# iv12-driver-board-v1.net
KiCad netlist of a schematic drawn in EAGLE
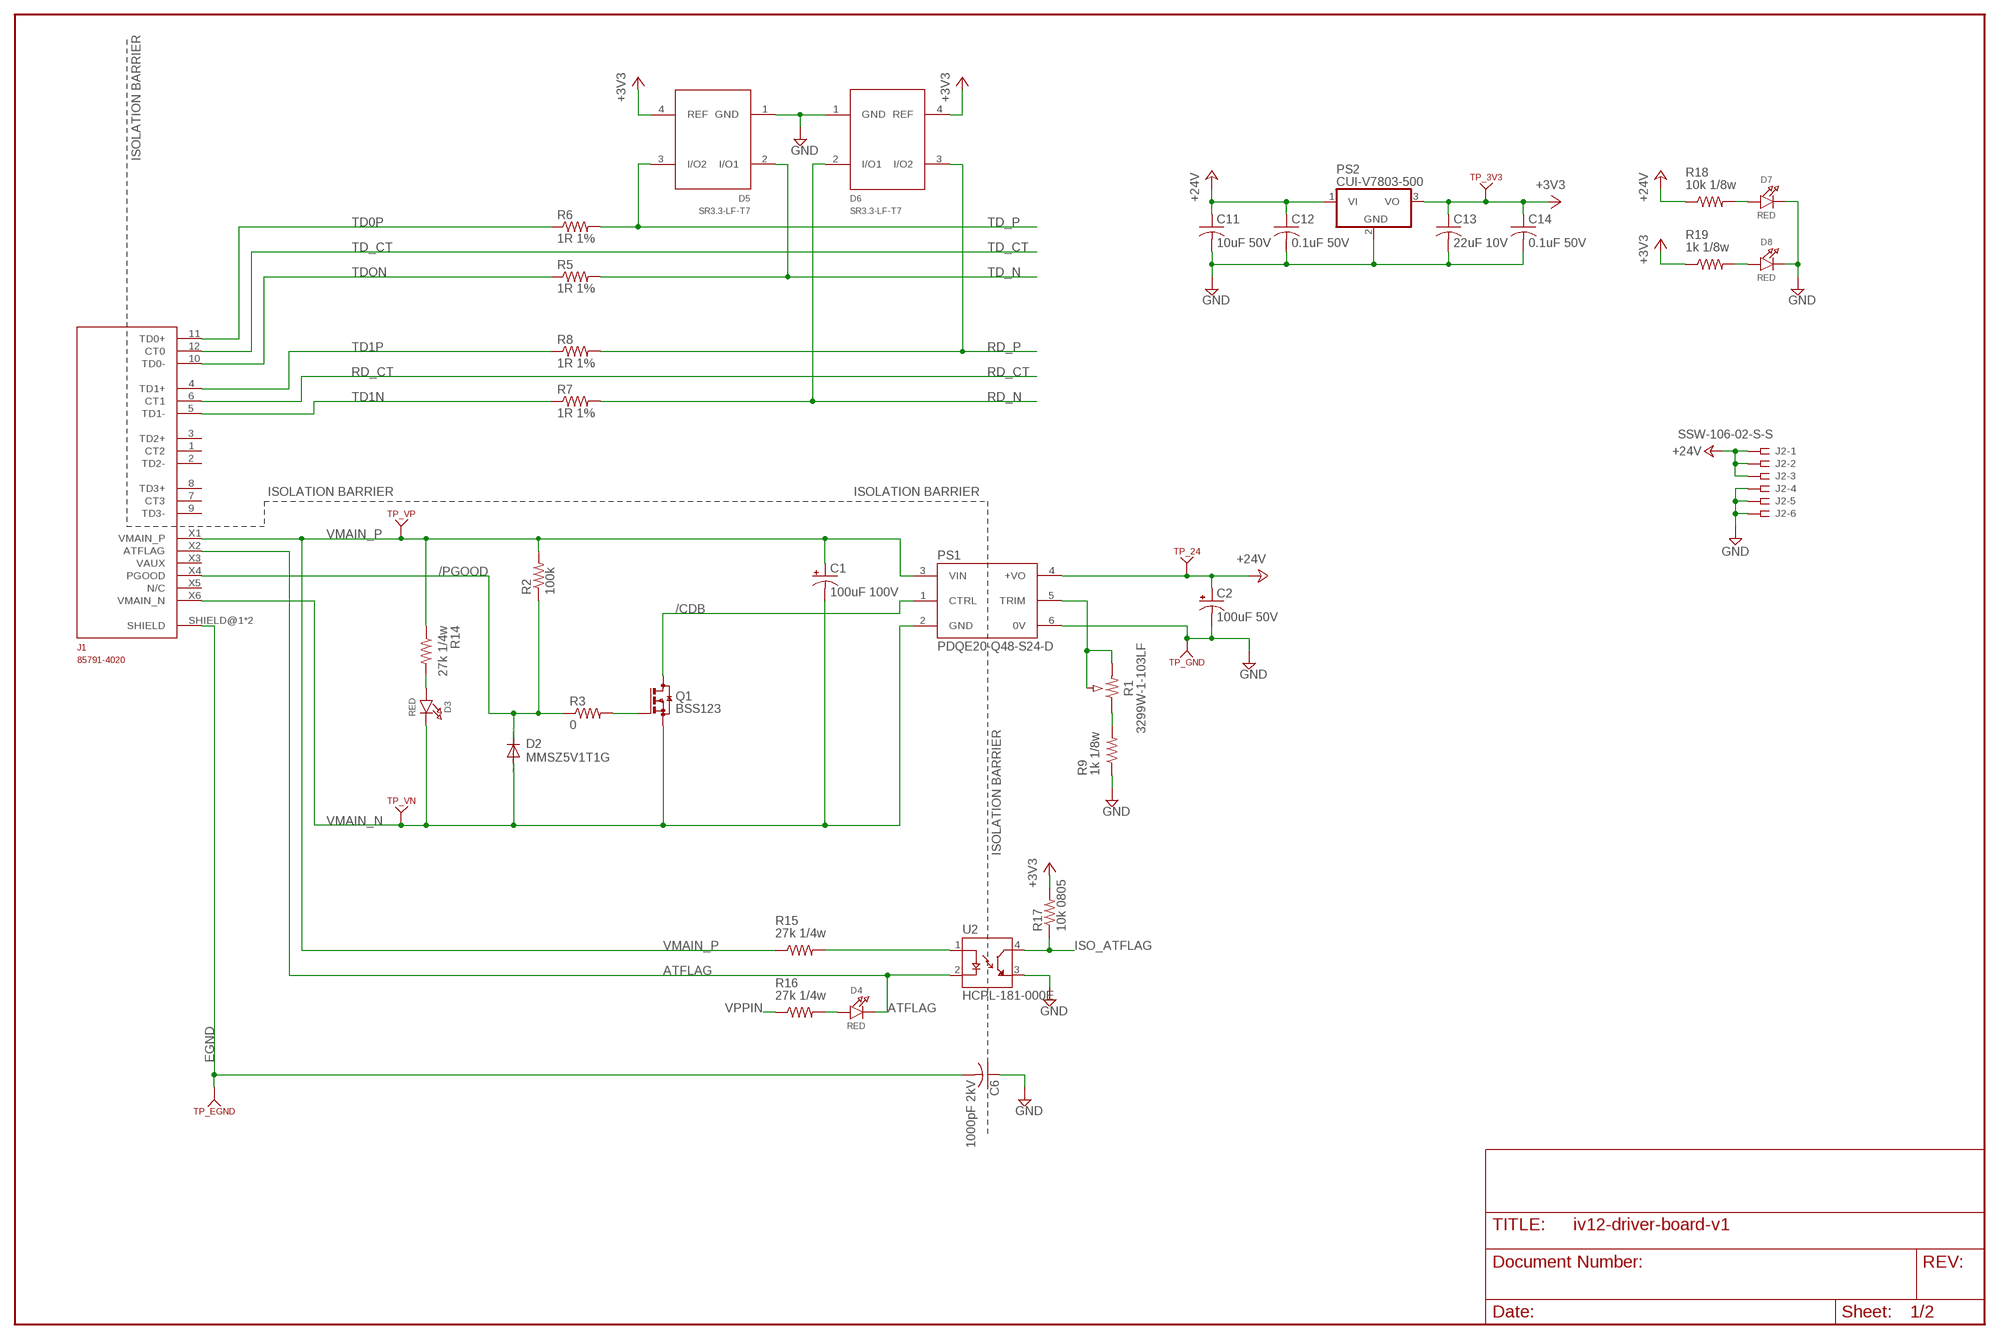
[diagram p0: schematic, sheet 1]
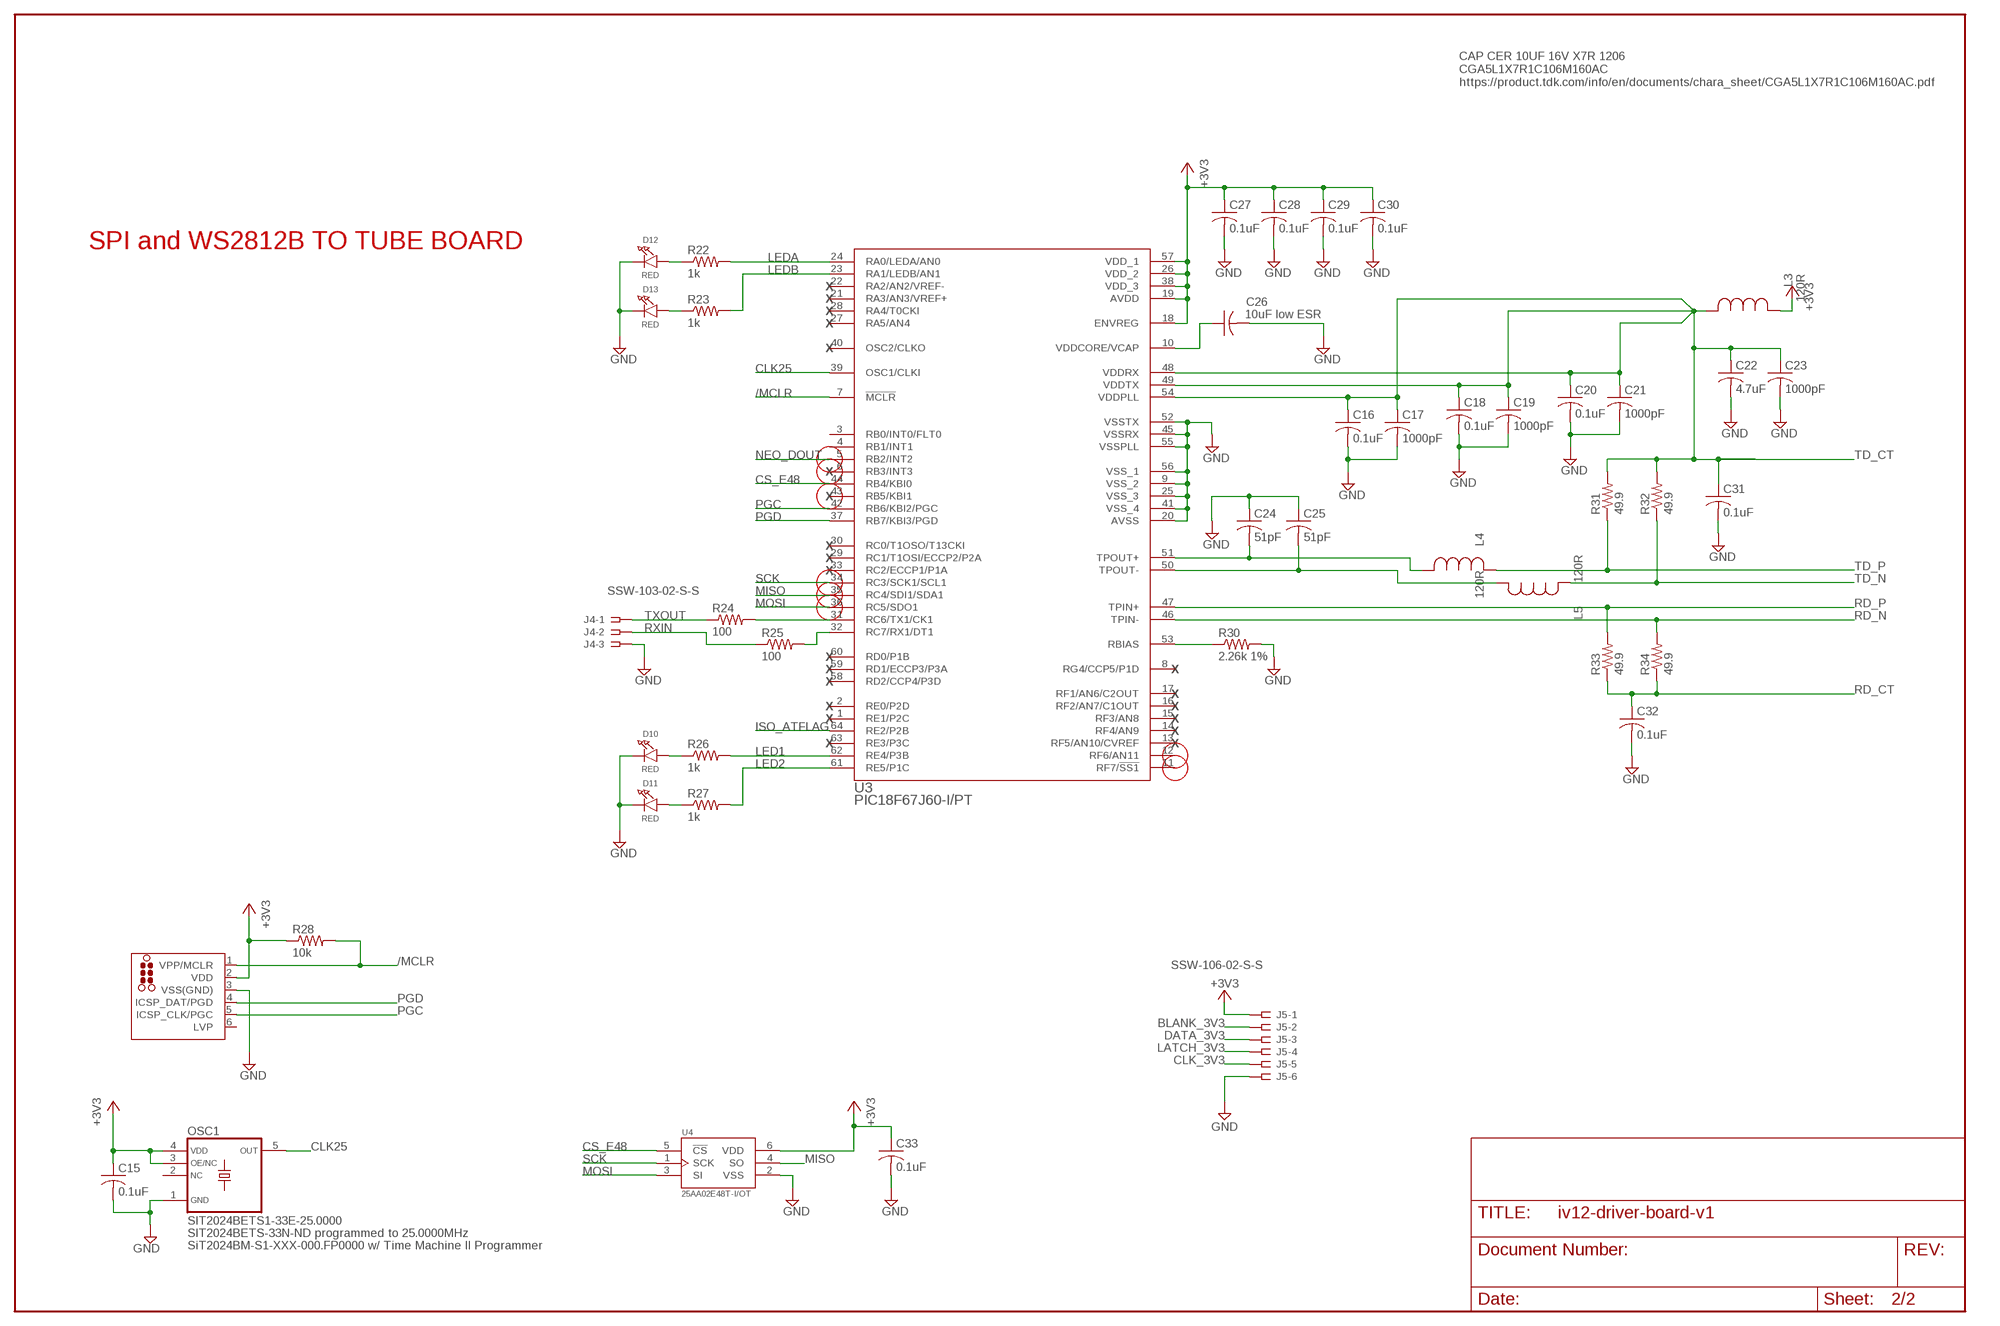
[diagram p1: schematic, sheet 2]

(export (version "E")
  (design (tool "Eeschema 10.0.6"))
  (components
    (comp (ref "C15")
      (value "0.1uF")
      (footprint "eagle-import:C0603")
      (libsource (lib "eagle-import") (part "C-USC0603"))
    )
    (comp (ref "C16")
      (value "0.1uF")
      (footprint "eagle-import:C0805")
      (libsource (lib "eagle-import") (part "C-USC0805"))
    )
    (comp (ref "C17")
      (value "1000pF")
      (footprint "eagle-import:C0805")
      (libsource (lib "eagle-import") (part "C-USC0805"))
    )
    (comp (ref "C18")
      (value "0.1uF")
      (footprint "eagle-import:C0805")
      (libsource (lib "eagle-import") (part "C-USC0805"))
    )
    (comp (ref "C19")
      (value "1000pF")
      (footprint "eagle-import:C0805")
      (libsource (lib "eagle-import") (part "C-USC0805"))
    )
    (comp (ref "C20")
      (value "0.1uF")
      (footprint "eagle-import:C0805")
      (libsource (lib "eagle-import") (part "C-USC0805"))
    )
    (comp (ref "C21")
      (value "1000pF")
      (footprint "eagle-import:C0805")
      (libsource (lib "eagle-import") (part "C-USC0805"))
    )
    (comp (ref "C22")
      (value "4.7uF")
      (footprint "eagle-import:C0805")
      (libsource (lib "eagle-import") (part "C-USC0805"))
    )
    (comp (ref "C23")
      (value "1000pF")
      (footprint "eagle-import:C0805")
      (libsource (lib "eagle-import") (part "C-USC0805"))
    )
    (comp (ref "C24")
      (value "51pF")
      (footprint "eagle-import:C0805")
      (libsource (lib "eagle-import") (part "C-USC0805"))
    )
    (comp (ref "C25")
      (value "51pF")
      (footprint "eagle-import:C0805")
      (libsource (lib "eagle-import") (part "C-USC0805"))
    )
    (comp (ref "C26")
      (value "10uF low ESR")
      (footprint "eagle-import:C1206")
      (libsource (lib "eagle-import") (part "resistor_C-USC1206"))
    )
    (comp (ref "C27")
      (value "0.1uF")
      (footprint "eagle-import:C0603")
      (libsource (lib "eagle-import") (part "C-USC0603"))
    )
    (comp (ref "C28")
      (value "0.1uF")
      (footprint "eagle-import:C0603")
      (libsource (lib "eagle-import") (part "C-USC0603"))
    )
    (comp (ref "C29")
      (value "0.1uF")
      (footprint "eagle-import:C0603")
      (libsource (lib "eagle-import") (part "C-USC0603"))
    )
    (comp (ref "C30")
      (value "0.1uF")
      (footprint "eagle-import:C0603")
      (libsource (lib "eagle-import") (part "C-USC0603"))
    )
    (comp (ref "C31")
      (value "0.1uF")
      (footprint "eagle-import:C0805")
      (libsource (lib "eagle-import") (part "C-USC0805"))
    )
    (comp (ref "C32")
      (value "0.1uF")
      (footprint "eagle-import:C0805")
      (libsource (lib "eagle-import") (part "C-USC0805"))
    )
    (comp (ref "C33")
      (value "0.1uF")
      (footprint "eagle-import:C0603")
      (libsource (lib "eagle-import") (part "C-USC0603"))
    )
    (comp (ref "D10")
      (value "RED")
      (footprint "eagle-import:CHIPLED_0805_NOOUTLINE")
      (libsource (lib "eagle-import") (part "LED0805_NOOUTLINE"))
    )
    (comp (ref "D11")
      (value "RED")
      (footprint "eagle-import:CHIPLED_0805_NOOUTLINE")
      (libsource (lib "eagle-import") (part "LED0805_NOOUTLINE"))
    )
    (comp (ref "D12")
      (value "RED")
      (footprint "eagle-import:CHIPLED_0805_NOOUTLINE")
      (libsource (lib "eagle-import") (part "LED0805_NOOUTLINE"))
    )
    (comp (ref "D13")
      (value "RED")
      (footprint "eagle-import:CHIPLED_0805_NOOUTLINE")
      (libsource (lib "eagle-import") (part "LED0805_NOOUTLINE"))
    )
    (comp (ref "J3")
      (value "TC2030-MCP-NL")
      (footprint "eagle-import:TC2030-MCP-NL")
      (libsource (lib "eagle-import") (part "TC2030-MCP-NL"))
    )
    (comp (ref "J4")
      (value "SSW-103-02-S-S")
      (footprint "eagle-import:SSW-103-02-S-S")
      (libsource (lib "eagle-import") (part "SSW-103-02-S-S"))
    )
    (comp (ref "J5")
      (value "SSW-106-02-S-S")
      (footprint "eagle-import:SSW-106-02-S-S")
      (libsource (lib "eagle-import") (part "SSW-106-02-S-S"))
    )
    (comp (ref "L3")
      (value "120R")
      (footprint "eagle-import:IND_1608-M")
      (fields (field (name "MANUFACTURER_PART_NUMBER") "MMZ1608B121CTAH0"))
      (libsource (lib "eagle-import") (part "MMZ1608B121CTAH0IND_1608-M"))
    )
    (comp (ref "L4")
      (value "120R")
      (footprint "eagle-import:IND_1608-M")
      (fields (field (name "MANUFACTURER_PART_NUMBER") "MMZ1608B121CTAH0"))
      (libsource (lib "eagle-import") (part "MMZ1608B121CTAH0IND_1608-M"))
    )
    (comp (ref "L5")
      (value "120R")
      (footprint "eagle-import:IND_1608-M")
      (fields (field (name "MANUFACTURER_PART_NUMBER") "MMZ1608B121CTAH0"))
      (libsource (lib "eagle-import") (part "MMZ1608B121CTAH0IND_1608-M"))
    )
    (comp (ref "OSC1")
      (value "SIT2024BETS1-33E-25.0000")
      (footprint "eagle-import:SOT23-5")
      (libsource (lib "eagle-import") (part "SIT2024BETS1-33E-10.0000"))
    )
    (comp (ref "R22")
      (value "1k")
      (footprint "eagle-import:R0805")
      (libsource (lib "eagle-import") (part "R-US_R0805"))
    )
    (comp (ref "R23")
      (value "1k")
      (footprint "eagle-import:R0805")
      (libsource (lib "eagle-import") (part "R-US_R0805"))
    )
    (comp (ref "R24")
      (value "100")
      (footprint "eagle-import:R0805")
      (libsource (lib "eagle-import") (part "R-US_R0805"))
    )
    (comp (ref "R25")
      (value "100")
      (footprint "eagle-import:R0805")
      (libsource (lib "eagle-import") (part "R-US_R0805"))
    )
    (comp (ref "R26")
      (value "1k")
      (footprint "eagle-import:R0805")
      (libsource (lib "eagle-import") (part "R-US_R0805"))
    )
    (comp (ref "R27")
      (value "1k")
      (footprint "eagle-import:R0805")
      (libsource (lib "eagle-import") (part "R-US_R0805"))
    )
    (comp (ref "R28")
      (value "10k")
      (footprint "eagle-import:R0805")
      (libsource (lib "eagle-import") (part "R-US_R0805"))
    )
    (comp (ref "R30")
      (value "2.26k 1%")
      (footprint "eagle-import:R0805")
      (libsource (lib "eagle-import") (part "R-US_R0805"))
    )
    (comp (ref "R31")
      (value "49.9")
      (footprint "eagle-import:R0805")
      (libsource (lib "eagle-import") (part "R-US_R0805"))
    )
    (comp (ref "R32")
      (value "49.9")
      (footprint "eagle-import:R0805")
      (libsource (lib "eagle-import") (part "R-US_R0805"))
    )
    (comp (ref "R33")
      (value "49.9")
      (footprint "eagle-import:R0805")
      (libsource (lib "eagle-import") (part "R-US_R0805"))
    )
    (comp (ref "R34")
      (value "49.9")
      (footprint "eagle-import:R0805")
      (libsource (lib "eagle-import") (part "R-US_R0805"))
    )
    (comp (ref "U3")
      (value "PIC18F67J60-I/PT")
      (footprint "eagle-import:TQFP64_10X10MC")
      (fields (field (name "MANUFACTURER_PART_NUMBER") "PIC18F67J60IPT"))
      (libsource (lib "eagle-import") (part "PIC18F67J60-I/PT"))
    )
    (comp (ref "U4")
      (value "25AA02E48T-I/OT")
      (footprint "eagle-import:SOT95P270X145-6N")
      (fields (field (name "DIGI-KEY_PART_NUMBER") "25AA02E48T-I/OTCT-ND") (field (name "MF") "Microchip"))
      (libsource (lib "eagle-import") (part "25AA02E48T-I/OT"))
    )
    (comp (ref "C1")
      (value "100uF 100V")
      (footprint "eagle-import:E5-13")
      (libsource (lib "eagle-import") (part "CPOL-USE5-13"))
    )
    (comp (ref "C2")
      (value "100uF 50V")
      (footprint "eagle-import:E5-10,5")
      (libsource (lib "eagle-import") (part "CPOL-USE5-10.5"))
    )
    (comp (ref "C6")
      (value "1000pF 2kV")
      (footprint "eagle-import:C1206K")
      (libsource (lib "eagle-import") (part "C-USC1206K"))
    )
    (comp (ref "C11")
      (value "10uF 50V")
      (footprint "eagle-import:C1210K")
      (fields (field (name "MFR") "KEMET") (field (name "MFR_PART_NO") "C1210C106K5RACTU"))
      (libsource (lib "eagle-import") (part "C-USC1210K"))
    )
    (comp (ref "C12")
      (value "0.1uF 50V")
      (footprint "eagle-import:C0805")
      (fields (field (name "MFR") "KEMET") (field (name "MFR_PART_NO") "C1206S104M5RACTU"))
      (libsource (lib "eagle-import") (part "C-USC0805"))
    )
    (comp (ref "C13")
      (value "22uF 10V")
      (footprint "eagle-import:C1206K")
      (fields (field (name "MFR") "KEMET") (field (name "MFR_PART_NO") "C1206C226K8RAC7800"))
      (libsource (lib "eagle-import") (part "C-USC1206K"))
    )
    (comp (ref "C14")
      (value "0.1uF 50V")
      (footprint "eagle-import:C0805")
      (fields (field (name "MFR") "KEMET") (field (name "MFR_PART_NO") "C1206S104M5RACTU"))
      (libsource (lib "eagle-import") (part "C-USC0805"))
    )
    (comp (ref "D2")
      (value "MMSZ5V1T1G")
      (footprint "eagle-import:SOD123")
      (libsource (lib "eagle-import") (part "DIODE-SOD123"))
    )
    (comp (ref "D3")
      (value "RED")
      (footprint "eagle-import:CHIPLED_0805_NOOUTLINE")
      (libsource (lib "eagle-import") (part "LED0805_NOOUTLINE"))
    )
    (comp (ref "D4")
      (value "RED")
      (footprint "eagle-import:CHIPLED_0805_NOOUTLINE")
      (libsource (lib "eagle-import") (part "LED0805_NOOUTLINE"))
    )
    (comp (ref "D5")
      (value "SR3.3-LF-T7")
      (footprint "eagle-import:SOT143B")
      (libsource (lib "eagle-import") (part "SR3.3-LF-T7"))
    )
    (comp (ref "D6")
      (value "SR3.3-LF-T7")
      (footprint "eagle-import:SOT143B")
      (libsource (lib "eagle-import") (part "SR3.3-LF-T7"))
    )
    (comp (ref "D7")
      (value "RED")
      (footprint "eagle-import:CHIPLED_0805_NOOUTLINE")
      (libsource (lib "eagle-import") (part "LED0805_NOOUTLINE"))
    )
    (comp (ref "D8")
      (value "RED")
      (footprint "eagle-import:CHIPLED_0805_NOOUTLINE")
      (libsource (lib "eagle-import") (part "LED0805_NOOUTLINE"))
    )
    (comp (ref "J1")
      (value "85791-4020")
      (footprint "eagle-import:85791-X020")
      (libsource (lib "eagle-import") (part "85791-4020"))
    )
    (comp (ref "J2")
      (value "SSW-106-02-S-S")
      (footprint "eagle-import:SSW-106-02-S-S")
      (libsource (lib "eagle-import") (part "SSW-106-02-S-S"))
    )
    (comp (ref "PS1")
      (value "PDQE20-Q48-S24-D")
      (footprint "eagle-import:CONV_PDQE20-Q48-S5-D")
      (fields
        (field (name "DIGI-KEY_PART_NUMBER") "102-6272-ND")
        (field (name "MF") "CUI Inc.")
        (field (name "MP") "PDQE20-Q48-S5-D")
      )
      (libsource (lib "eagle-import") (part "PDQE20-Q48-S5-D"))
    )
    (comp (ref "PS2")
      (value "CUI-V7803-500")
      (footprint "eagle-import:CUI-78XX-500")
      (libsource (lib "eagle-import") (part "CUI-V7803-500"))
    )
    (comp (ref "Q1")
      (value "BSS123")
      (footprint "eagle-import:SOT23")
      (libsource (lib "eagle-import") (part "BSS123"))
    )
    (comp (ref "R1")
      (value "3299W-1-103LF")
      (footprint "eagle-import:POT_3299W")
      (libsource (lib "eagle-import") (part "3299W-1-103LF"))
    )
    (comp (ref "R2")
      (value "100k")
      (footprint "eagle-import:R0805")
      (libsource (lib "eagle-import") (part "resistor_R-US_R0805"))
    )
    (comp (ref "R3")
      (value "0")
      (footprint "eagle-import:R0805")
      (libsource (lib "eagle-import") (part "resistor_R-US_R0805"))
    )
    (comp (ref "R5")
      (value "1R 1%")
      (footprint "eagle-import:R0805")
      (libsource (lib "eagle-import") (part "R-US_R0805"))
    )
    (comp (ref "R6")
      (value "1R 1%")
      (footprint "eagle-import:R0805")
      (libsource (lib "eagle-import") (part "R-US_R0805"))
    )
    (comp (ref "R7")
      (value "1R 1%")
      (footprint "eagle-import:R0805")
      (libsource (lib "eagle-import") (part "R-US_R0805"))
    )
    (comp (ref "R8")
      (value "1R 1%")
      (footprint "eagle-import:R0805")
      (libsource (lib "eagle-import") (part "R-US_R0805"))
    )
    (comp (ref "R9")
      (value "1k 1/8w")
      (footprint "eagle-import:R0805")
      (libsource (lib "eagle-import") (part "R-US_R0805"))
    )
    (comp (ref "R14")
      (value "27k 1/4w")
      (footprint "eagle-import:R1206")
      (libsource (lib "eagle-import") (part "R-US_R1206"))
    )
    (comp (ref "R15")
      (value "27k 1/4w")
      (footprint "eagle-import:R1206")
      (libsource (lib "eagle-import") (part "R-US_R1206"))
    )
    (comp (ref "R16")
      (value "27k 1/4w")
      (footprint "eagle-import:R1206")
      (libsource (lib "eagle-import") (part "R-US_R1206"))
    )
    (comp (ref "R17")
      (value "10k 0805")
      (footprint "eagle-import:R0805")
      (libsource (lib "eagle-import") (part "resistor_R-US_R0805"))
    )
    (comp (ref "R18")
      (value "10k 1/8w")
      (footprint "eagle-import:R0805")
      (libsource (lib "eagle-import") (part "R-US_R0805"))
    )
    (comp (ref "R19")
      (value "1k 1/8w")
      (footprint "eagle-import:R0805")
      (libsource (lib "eagle-import") (part "R-US_R0805"))
    )
    (comp (ref "TP_3V3")
      (value "KEYSTONE_500X")
      (footprint "eagle-import:KEYSTONE_TP500X")
      (libsource (lib "eagle-import") (part "KEYSTONE_500X"))
    )
    (comp (ref "TP_24")
      (value "KEYSTONE_500X")
      (footprint "eagle-import:KEYSTONE_TP500X")
      (libsource (lib "eagle-import") (part "KEYSTONE_500X"))
    )
    (comp (ref "TP_EGND")
      (value "KEYSTONE_500X")
      (footprint "eagle-import:KEYSTONE_TP500X")
      (libsource (lib "eagle-import") (part "KEYSTONE_500X"))
    )
    (comp (ref "TP_GND")
      (value "KEYSTONE_500X")
      (footprint "eagle-import:KEYSTONE_TP500X")
      (libsource (lib "eagle-import") (part "KEYSTONE_500X"))
    )
    (comp (ref "TP_VN")
      (value "KEYSTONE_500X")
      (footprint "eagle-import:KEYSTONE_TP500X")
      (libsource (lib "eagle-import") (part "KEYSTONE_500X"))
    )
    (comp (ref "TP_VP")
      (value "KEYSTONE_500X")
      (footprint "eagle-import:KEYSTONE_TP500X")
      (libsource (lib "eagle-import") (part "KEYSTONE_500X"))
    )
    (comp (ref "U2")
      (value "HCPL-181-000E")
      (footprint "eagle-import:SOIC254P675X240-4N")
      (fields (field (name "DIGI-KEY_PART_NUMBER") "516-1646-1-ND") (field (name "MF") "Broadcom Limited"))
      (libsource (lib "eagle-import") (part "HCPL-181-000E"))
    )
  )
  (nets
    (net (code "1") (name "+3V3") (class "Default")
      (node (ref "C13") (pin "1") (pinfunction "1_1") (pintype "passive"))
      (node (ref "C14") (pin "1") (pinfunction "1_1") (pintype "passive"))
      (node (ref "C15") (pin "1") (pinfunction "1_1") (pintype "passive"))
      (node (ref "C27") (pin "1") (pinfunction "1_1") (pintype "passive"))
      (node (ref "C28") (pin "1") (pinfunction "1_1") (pintype "passive"))
      (node (ref "C29") (pin "1") (pinfunction "1_1") (pintype "passive"))
      (node (ref "C30") (pin "1") (pinfunction "1_1") (pintype "passive"))
      (node (ref "C33") (pin "1") (pinfunction "1_1") (pintype "passive"))
      (node (ref "D5") (pin "4") (pinfunction "REF_4") (pintype "bidirectional"))
      (node (ref "D6") (pin "4") (pinfunction "REF_4") (pintype "bidirectional"))
      (node (ref "J3") (pin "2") (pinfunction "VDD_2") (pintype "power_in"))
      (node (ref "J5") (pin "1") (pinfunction "1_1") (pintype "passive"))
      (node (ref "L3") (pin "2") (pinfunction "2_2") (pintype "passive"))
      (node (ref "OSC1") (pin "3") (pinfunction "OE/NC_3") (pintype "bidirectional"))
      (node (ref "OSC1") (pin "4") (pinfunction "VDD_4") (pintype "bidirectional"))
      (node (ref "PS2") (pin "3") (pinfunction "VO_3") (pintype "passive"))
      (node (ref "R17") (pin "2") (pinfunction "2_2") (pintype "passive"))
      (node (ref "R19") (pin "1") (pinfunction "1_1") (pintype "passive"))
      (node (ref "R28") (pin "1") (pinfunction "1_1") (pintype "passive"))
      (node (ref "TP_3V3") (pin "1") (pinfunction "P$1_1") (pintype "bidirectional"))
      (node (ref "U3") (pin "18") (pinfunction "ENVREG_18") (pintype "passive"))
      (node (ref "U3") (pin "19") (pinfunction "AVDD_19") (pintype "passive"))
      (node (ref "U3") (pin "26") (pinfunction "VDD_2_26") (pintype "passive"))
      (node (ref "U3") (pin "38") (pinfunction "VDD_3_38") (pintype "passive"))
      (node (ref "U3") (pin "57") (pinfunction "VDD_1_57") (pintype "passive"))
      (node (ref "U4") (pin "6") (pinfunction "VDD_6") (pintype "power_in"))
    )
    (net (code "2") (name "+24V") (class "Default")
      (node (ref "C11") (pin "1") (pinfunction "1_1") (pintype "passive"))
      (node (ref "C12") (pin "1") (pinfunction "1_1") (pintype "passive"))
      (node (ref "C2") (pin "+") (pinfunction "+_+") (pintype "passive"))
      (node (ref "J2") (pin "1") (pinfunction "1_1") (pintype "passive"))
      (node (ref "J2") (pin "2") (pinfunction "1_2") (pintype "passive"))
      (node (ref "J2") (pin "3") (pinfunction "1_3") (pintype "passive"))
      (node (ref "PS1") (pin "4") (pinfunction "+VO_4") (pintype "output"))
      (node (ref "PS2") (pin "1") (pinfunction "VI_1") (pintype "input"))
      (node (ref "R18") (pin "1") (pinfunction "1_1") (pintype "passive"))
      (node (ref "TP_24") (pin "1") (pinfunction "P$1_1") (pintype "bidirectional"))
    )
    (net (code "3") (name "ATFLAG") (class "Default")
      (node (ref "D4") (pin "C") (pinfunction "C_C") (pintype "passive"))
      (node (ref "J1") (pin "X2") (pinfunction "ATFLAG_X2") (pintype "bidirectional"))
      (node (ref "U2") (pin "2") (pinfunction "CATHODE_2") (pintype "passive"))
    )
    (net (code "4") (name "BLANK_3V3") (class "Default")
      (node (ref "J5") (pin "2") (pinfunction "1_2") (pintype "passive"))
    )
    (net (code "5") (name "CLK25") (class "Default")
      (node (ref "OSC1") (pin "5") (pinfunction "OUT_5") (pintype "bidirectional"))
      (node (ref "U3") (pin "39") (pinfunction "OSC1/CLKI_39") (pintype "passive"))
    )
    (net (code "6") (name "CLK_3V3") (class "Default")
      (node (ref "J5") (pin "5") (pinfunction "1_5") (pintype "passive"))
    )
    (net (code "7") (name "CS_E48") (class "Default")
      (node (ref "U3") (pin "44") (pinfunction "RB4/KBI0_44") (pintype "passive"))
      (node (ref "U4") (pin "5") (pinfunction "~{CS}_5") (pintype "input"))
    )
    (net (code "8") (name "DATA_3V3") (class "Default")
      (node (ref "J5") (pin "3") (pinfunction "1_3") (pintype "passive"))
    )
    (net (code "9") (name "EGND") (class "Default")
      (node (ref "C6") (pin "2") (pinfunction "2_2") (pintype "passive"))
      (node (ref "J1") (pin "SHIELD@1") (pinfunction "SHIELD_SHIELD@1") (pintype "bidirectional"))
      (node (ref "J1") (pin "SHIELD@2") (pinfunction "SHIELD_SHIELD@2") (pintype "bidirectional"))
      (node (ref "TP_EGND") (pin "1") (pinfunction "P$1_1") (pintype "bidirectional"))
    )
    (net (code "10") (name "GND") (class "Default")
      (node (ref "C11") (pin "2") (pinfunction "2_2") (pintype "passive"))
      (node (ref "C12") (pin "2") (pinfunction "2_2") (pintype "passive"))
      (node (ref "C13") (pin "2") (pinfunction "2_2") (pintype "passive"))
      (node (ref "C14") (pin "2") (pinfunction "2_2") (pintype "passive"))
      (node (ref "C15") (pin "2") (pinfunction "2_2") (pintype "passive"))
      (node (ref "C16") (pin "2") (pinfunction "2_2") (pintype "passive"))
      (node (ref "C17") (pin "2") (pinfunction "2_2") (pintype "passive"))
      (node (ref "C18") (pin "2") (pinfunction "2_2") (pintype "passive"))
      (node (ref "C19") (pin "2") (pinfunction "2_2") (pintype "passive"))
      (node (ref "C2") (pin "-") (pinfunction "-_-") (pintype "passive"))
      (node (ref "C20") (pin "2") (pinfunction "2_2") (pintype "passive"))
      (node (ref "C21") (pin "2") (pinfunction "2_2") (pintype "passive"))
      (node (ref "C22") (pin "2") (pinfunction "2_2") (pintype "passive"))
      (node (ref "C23") (pin "2") (pinfunction "2_2") (pintype "passive"))
      (node (ref "C24") (pin "1") (pinfunction "1_1") (pintype "passive"))
      (node (ref "C25") (pin "1") (pinfunction "1_1") (pintype "passive"))
      (node (ref "C26") (pin "2") (pinfunction "2_2") (pintype "passive"))
      (node (ref "C27") (pin "2") (pinfunction "2_2") (pintype "passive"))
      (node (ref "C28") (pin "2") (pinfunction "2_2") (pintype "passive"))
      (node (ref "C29") (pin "2") (pinfunction "2_2") (pintype "passive"))
      (node (ref "C30") (pin "2") (pinfunction "2_2") (pintype "passive"))
      (node (ref "C31") (pin "2") (pinfunction "2_2") (pintype "passive"))
      (node (ref "C32") (pin "2") (pinfunction "2_2") (pintype "passive"))
      (node (ref "C33") (pin "2") (pinfunction "2_2") (pintype "passive"))
      (node (ref "C6") (pin "1") (pinfunction "1_1") (pintype "passive"))
      (node (ref "D10") (pin "C") (pinfunction "C_C") (pintype "passive"))
      (node (ref "D11") (pin "C") (pinfunction "C_C") (pintype "passive"))
      (node (ref "D12") (pin "C") (pinfunction "C_C") (pintype "passive"))
      (node (ref "D13") (pin "C") (pinfunction "C_C") (pintype "passive"))
      (node (ref "D5") (pin "1") (pinfunction "GND_1") (pintype "bidirectional"))
      (node (ref "D6") (pin "1") (pinfunction "GND_1") (pintype "bidirectional"))
      (node (ref "D7") (pin "C") (pinfunction "C_C") (pintype "passive"))
      (node (ref "D8") (pin "C") (pinfunction "C_C") (pintype "passive"))
      (node (ref "J2") (pin "4") (pinfunction "1_4") (pintype "passive"))
      (node (ref "J2") (pin "5") (pinfunction "1_5") (pintype "passive"))
      (node (ref "J2") (pin "6") (pinfunction "1_6") (pintype "passive"))
      (node (ref "J3") (pin "3") (pinfunction "VSS(GND)_3") (pintype "power_in"))
      (node (ref "J4") (pin "3") (pinfunction "1_3") (pintype "passive"))
      (node (ref "J5") (pin "6") (pinfunction "1_6") (pintype "passive"))
      (node (ref "OSC1") (pin "1") (pinfunction "GND_1") (pintype "bidirectional"))
      (node (ref "PS1") (pin "6") (pinfunction "0V_6") (pintype "output"))
      (node (ref "PS2") (pin "2") (pinfunction "GND_2") (pintype "passive"))
      (node (ref "R30") (pin "2") (pinfunction "2_2") (pintype "passive"))
      (node (ref "R9") (pin "1") (pinfunction "1_1") (pintype "passive"))
      (node (ref "TP_GND") (pin "1") (pinfunction "P$1_1") (pintype "bidirectional"))
      (node (ref "U2") (pin "3") (pinfunction "EMITTER_3") (pintype "passive"))
      (node (ref "U3") (pin "20") (pinfunction "AVSS_20") (pintype "passive"))
      (node (ref "U3") (pin "25") (pinfunction "VSS_3_25") (pintype "passive"))
      (node (ref "U3") (pin "41") (pinfunction "VSS_4_41") (pintype "passive"))
      (node (ref "U3") (pin "45") (pinfunction "VSSRX_45") (pintype "passive"))
      (node (ref "U3") (pin "52") (pinfunction "VSSTX_52") (pintype "passive"))
      (node (ref "U3") (pin "55") (pinfunction "VSSPLL_55") (pintype "passive"))
      (node (ref "U3") (pin "56") (pinfunction "VSS_1_56") (pintype "passive"))
      (node (ref "U3") (pin "9") (pinfunction "VSS_2_9") (pintype "passive"))
      (node (ref "U4") (pin "2") (pinfunction "VSS_2") (pintype "power_in"))
    )
    (net (code "11") (name "ISO_ATFLAG") (class "Default")
      (node (ref "R17") (pin "1") (pinfunction "1_1") (pintype "passive"))
      (node (ref "U2") (pin "4") (pinfunction "COLLECTOR_4") (pintype "passive"))
      (node (ref "U3") (pin "64") (pinfunction "RE2/P2B_64") (pintype "passive"))
    )
    (net (code "12") (name "LATCH_3V3") (class "Default")
      (node (ref "J5") (pin "4") (pinfunction "1_4") (pintype "passive"))
    )
    (net (code "13") (name "LED1") (class "Default")
      (node (ref "R26") (pin "2") (pinfunction "2_2") (pintype "passive"))
      (node (ref "U3") (pin "62") (pinfunction "RE4/P3B_62") (pintype "passive"))
    )
    (net (code "14") (name "LED2") (class "Default")
      (node (ref "R27") (pin "2") (pinfunction "2_2") (pintype "passive"))
      (node (ref "U3") (pin "61") (pinfunction "RE5/P1C_61") (pintype "passive"))
    )
    (net (code "15") (name "LEDA") (class "Default")
      (node (ref "R22") (pin "2") (pinfunction "2_2") (pintype "passive"))
      (node (ref "U3") (pin "24") (pinfunction "RA0/LEDA/AN0_24") (pintype "passive"))
    )
    (net (code "16") (name "LEDB") (class "Default")
      (node (ref "R23") (pin "2") (pinfunction "2_2") (pintype "passive"))
      (node (ref "U3") (pin "23") (pinfunction "RA1/LEDB/AN1_23") (pintype "passive"))
    )
    (net (code "17") (name "MISO") (class "Default")
      (node (ref "U3") (pin "35") (pinfunction "RC4/SDI1/SDA1_35") (pintype "passive"))
      (node (ref "U4") (pin "4") (pinfunction "SO_4") (pintype "output"))
    )
    (net (code "18") (name "MOSI") (class "Default")
      (node (ref "U3") (pin "36") (pinfunction "RC5/SDO1_36") (pintype "passive"))
      (node (ref "U4") (pin "3") (pinfunction "SI_3") (pintype "input"))
    )
    (net (code "19") (name "NEO_DOUT") (class "Default")
      (node (ref "U3") (pin "5") (pinfunction "RB2/INT2_5") (pintype "passive"))
    )
    (net (code "20") (name "Net-(D3-PadA)") (class "Default")
      (node (ref "D3") (pin "A") (pinfunction "A_A") (pintype "passive"))
      (node (ref "R14") (pin "2") (pinfunction "2_2") (pintype "passive"))
    )
    (net (code "21") (name "Net-(D4-PadA)") (class "Default")
      (node (ref "D4") (pin "A") (pinfunction "A_A") (pintype "passive"))
      (node (ref "R16") (pin "2") (pinfunction "2_2") (pintype "passive"))
    )
    (net (code "22") (name "Net-(D7-PadA)") (class "Default")
      (node (ref "D7") (pin "A") (pinfunction "A_A") (pintype "passive"))
      (node (ref "R18") (pin "2") (pinfunction "2_2") (pintype "passive"))
    )
    (net (code "23") (name "Net-(D8-PadA)") (class "Default")
      (node (ref "D8") (pin "A") (pinfunction "A_A") (pintype "passive"))
      (node (ref "R19") (pin "2") (pinfunction "2_2") (pintype "passive"))
    )
    (net (code "24") (name "Net-(D10-PadA)") (class "Default")
      (node (ref "D10") (pin "A") (pinfunction "A_A") (pintype "passive"))
      (node (ref "R26") (pin "1") (pinfunction "1_1") (pintype "passive"))
    )
    (net (code "25") (name "Net-(D11-PadA)") (class "Default")
      (node (ref "D11") (pin "A") (pinfunction "A_A") (pintype "passive"))
      (node (ref "R27") (pin "1") (pinfunction "1_1") (pintype "passive"))
    )
    (net (code "26") (name "Net-(D12-PadA)") (class "Default")
      (node (ref "D12") (pin "A") (pinfunction "A_A") (pintype "passive"))
      (node (ref "R22") (pin "1") (pinfunction "1_1") (pintype "passive"))
    )
    (net (code "27") (name "Net-(D13-PadA)") (class "Default")
      (node (ref "D13") (pin "A") (pinfunction "A_A") (pintype "passive"))
      (node (ref "R23") (pin "1") (pinfunction "1_1") (pintype "passive"))
    )
    (net (code "28") (name "Net-(PS1-TRIM)") (class "Default")
      (node (ref "PS1") (pin "5") (pinfunction "TRIM_5") (pintype "passive"))
      (node (ref "R1") (pin "2") (pinfunction "2_2") (pintype "passive"))
      (node (ref "R1") (pin "3") (pinfunction "3_3") (pintype "passive"))
    )
    (net (code "29") (name "Net-(Q1-G)") (class "Default")
      (node (ref "Q1") (pin "1") (pinfunction "G_1") (pintype "passive"))
      (node (ref "R3") (pin "2") (pinfunction "2_2") (pintype "passive"))
    )
    (net (code "30") (name "Net-(R1-Pad1)") (class "Default")
      (node (ref "R1") (pin "1") (pinfunction "1_1") (pintype "passive"))
      (node (ref "R9") (pin "2") (pinfunction "2_2") (pintype "passive"))
    )
    (net (code "31") (name "Net-(U2-ANODE)") (class "Default")
      (node (ref "R15") (pin "2") (pinfunction "2_2") (pintype "passive"))
      (node (ref "U2") (pin "1") (pinfunction "ANODE_1") (pintype "passive"))
    )
    (net (code "32") (name "Net-(U3-RBIAS)") (class "Default")
      (node (ref "R30") (pin "1") (pinfunction "1_1") (pintype "passive"))
      (node (ref "U3") (pin "53") (pinfunction "RBIAS_53") (pintype "passive"))
    )
    (net (code "33") (name "Net-(U3-RC6{slash}TX1{slash}CK1)") (class "Default")
      (node (ref "R24") (pin "2") (pinfunction "2_2") (pintype "passive"))
      (node (ref "U3") (pin "31") (pinfunction "RC6/TX1/CK1_31") (pintype "passive"))
    )
    (net (code "34") (name "Net-(U3-RC7{slash}RX1{slash}DT1)") (class "Default")
      (node (ref "R25") (pin "2") (pinfunction "2_2") (pintype "passive"))
      (node (ref "U3") (pin "32") (pinfunction "RC7/RX1/DT1_32") (pintype "passive"))
    )
    (net (code "35") (name "Net-(U3-TPOUT+)") (class "Default")
      (node (ref "C24") (pin "2") (pinfunction "2_2") (pintype "passive"))
      (node (ref "L4") (pin "1") (pinfunction "1_1") (pintype "passive"))
      (node (ref "U3") (pin "51") (pinfunction "TPOUT+_51") (pintype "passive"))
    )
    (net (code "36") (name "Net-(U3-TPOUT-)") (class "Default")
      (node (ref "C25") (pin "2") (pinfunction "2_2") (pintype "passive"))
      (node (ref "L5") (pin "1") (pinfunction "1_1") (pintype "passive"))
      (node (ref "U3") (pin "50") (pinfunction "TPOUT-_50") (pintype "passive"))
    )
    (net (code "37") (name "Net-(U3-VDDCORE{slash}VCAP)") (class "Default")
      (node (ref "C26") (pin "1") (pinfunction "1_1") (pintype "passive"))
      (node (ref "U3") (pin "10") (pinfunction "VDDCORE/VCAP_10") (pintype "passive"))
    )
    (net (code "38") (name "PGC") (class "Default")
      (node (ref "J3") (pin "5") (pinfunction "ICSP_CLK/PGC_5") (pintype "output"))
      (node (ref "U3") (pin "42") (pinfunction "RB6/KBI2/PGC_42") (pintype "passive"))
    )
    (net (code "39") (name "PGD") (class "Default")
      (node (ref "J3") (pin "4") (pinfunction "ICSP_DAT/PGD_4") (pintype "bidirectional"))
      (node (ref "U3") (pin "37") (pinfunction "RB7/KBI3/PGD_37") (pintype "passive"))
    )
    (net (code "40") (name "RD_CT") (class "Default")
      (node (ref "C32") (pin "1") (pinfunction "1_1") (pintype "passive"))
      (node (ref "J1") (pin "6") (pinfunction "CT1_6") (pintype "bidirectional"))
      (node (ref "R33") (pin "1") (pinfunction "1_1") (pintype "passive"))
      (node (ref "R34") (pin "1") (pinfunction "1_1") (pintype "passive"))
    )
    (net (code "41") (name "RD_N") (class "Default")
      (node (ref "D6") (pin "2") (pinfunction "I/O1_2") (pintype "bidirectional"))
      (node (ref "R34") (pin "2") (pinfunction "2_2") (pintype "passive"))
      (node (ref "R7") (pin "2") (pinfunction "2_2") (pintype "passive"))
      (node (ref "U3") (pin "46") (pinfunction "TPIN-_46") (pintype "passive"))
    )
    (net (code "42") (name "RD_P") (class "Default")
      (node (ref "D6") (pin "3") (pinfunction "I/O2_3") (pintype "bidirectional"))
      (node (ref "R33") (pin "2") (pinfunction "2_2") (pintype "passive"))
      (node (ref "R8") (pin "2") (pinfunction "2_2") (pintype "passive"))
      (node (ref "U3") (pin "47") (pinfunction "TPIN+_47") (pintype "passive"))
    )
    (net (code "43") (name "RXIN") (class "Default")
      (node (ref "J4") (pin "2") (pinfunction "1_2") (pintype "passive"))
      (node (ref "R25") (pin "1") (pinfunction "1_1") (pintype "passive"))
    )
    (net (code "44") (name "SCK") (class "Default")
      (node (ref "U3") (pin "34") (pinfunction "RC3/SCK1/SCL1_34") (pintype "passive"))
      (node (ref "U4") (pin "1") (pinfunction "SCK_1") (pintype "input"))
    )
    (net (code "45") (name "TD0P") (class "Default")
      (node (ref "J1") (pin "11") (pinfunction "TD0+_11") (pintype "bidirectional"))
      (node (ref "R6") (pin "1") (pinfunction "1_1") (pintype "passive"))
    )
    (net (code "46") (name "TD1N") (class "Default")
      (node (ref "J1") (pin "5") (pinfunction "TD1-_5") (pintype "bidirectional"))
      (node (ref "R7") (pin "1") (pinfunction "1_1") (pintype "passive"))
    )
    (net (code "47") (name "TD1P") (class "Default")
      (node (ref "J1") (pin "4") (pinfunction "TD1+_4") (pintype "bidirectional"))
      (node (ref "R8") (pin "1") (pinfunction "1_1") (pintype "passive"))
    )
    (net (code "48") (name "TDON") (class "Default")
      (node (ref "J1") (pin "10") (pinfunction "TD0-_10") (pintype "bidirectional"))
      (node (ref "R5") (pin "1") (pinfunction "1_1") (pintype "passive"))
    )
    (net (code "49") (name "TD_CT") (class "Default")
      (node (ref "C16") (pin "1") (pinfunction "1_1") (pintype "passive"))
      (node (ref "C17") (pin "1") (pinfunction "1_1") (pintype "passive"))
      (node (ref "C18") (pin "1") (pinfunction "1_1") (pintype "passive"))
      (node (ref "C19") (pin "1") (pinfunction "1_1") (pintype "passive"))
      (node (ref "C20") (pin "1") (pinfunction "1_1") (pintype "passive"))
      (node (ref "C21") (pin "1") (pinfunction "1_1") (pintype "passive"))
      (node (ref "C22") (pin "1") (pinfunction "1_1") (pintype "passive"))
      (node (ref "C23") (pin "1") (pinfunction "1_1") (pintype "passive"))
      (node (ref "C31") (pin "1") (pinfunction "1_1") (pintype "passive"))
      (node (ref "J1") (pin "12") (pinfunction "CT0_12") (pintype "bidirectional"))
      (node (ref "L3") (pin "1") (pinfunction "1_1") (pintype "passive"))
      (node (ref "R31") (pin "2") (pinfunction "2_2") (pintype "passive"))
      (node (ref "R32") (pin "2") (pinfunction "2_2") (pintype "passive"))
      (node (ref "U3") (pin "48") (pinfunction "VDDRX_48") (pintype "passive"))
      (node (ref "U3") (pin "49") (pinfunction "VDDTX_49") (pintype "passive"))
      (node (ref "U3") (pin "54") (pinfunction "VDDPLL_54") (pintype "passive"))
    )
    (net (code "50") (name "TD_N") (class "Default")
      (node (ref "D5") (pin "2") (pinfunction "I/O1_2") (pintype "bidirectional"))
      (node (ref "L5") (pin "2") (pinfunction "2_2") (pintype "passive"))
      (node (ref "R32") (pin "1") (pinfunction "1_1") (pintype "passive"))
      (node (ref "R5") (pin "2") (pinfunction "2_2") (pintype "passive"))
    )
    (net (code "51") (name "TD_P") (class "Default")
      (node (ref "D5") (pin "3") (pinfunction "I/O2_3") (pintype "bidirectional"))
      (node (ref "L4") (pin "2") (pinfunction "2_2") (pintype "passive"))
      (node (ref "R31") (pin "1") (pinfunction "1_1") (pintype "passive"))
      (node (ref "R6") (pin "2") (pinfunction "2_2") (pintype "passive"))
    )
    (net (code "52") (name "TXOUT") (class "Default")
      (node (ref "J4") (pin "1") (pinfunction "1_1") (pintype "passive"))
      (node (ref "R24") (pin "1") (pinfunction "1_1") (pintype "passive"))
    )
    (net (code "53") (name "VMAIN_N") (class "Default")
      (node (ref "C1") (pin "-") (pinfunction "-_-") (pintype "passive"))
      (node (ref "D2") (pin "A") (pinfunction "A_A") (pintype "passive"))
      (node (ref "D3") (pin "C") (pinfunction "C_C") (pintype "passive"))
      (node (ref "J1") (pin "X6") (pinfunction "VMAIN_N_X6") (pintype "bidirectional"))
      (node (ref "PS1") (pin "2") (pinfunction "GND_2") (pintype "power_in"))
      (node (ref "Q1") (pin "2") (pinfunction "S_2") (pintype "passive"))
      (node (ref "TP_VN") (pin "1") (pinfunction "P$1_1") (pintype "bidirectional"))
    )
    (net (code "54") (name "VMAIN_P") (class "Default")
      (node (ref "C1") (pin "+") (pinfunction "+_+") (pintype "passive"))
      (node (ref "J1") (pin "X1") (pinfunction "VMAIN_P_X1") (pintype "bidirectional"))
      (node (ref "PS1") (pin "3") (pinfunction "VIN_3") (pintype "input"))
      (node (ref "R14") (pin "1") (pinfunction "1_1") (pintype "passive"))
      (node (ref "R15") (pin "1") (pinfunction "1_1") (pintype "passive"))
      (node (ref "R2") (pin "2") (pinfunction "2_2") (pintype "passive"))
      (node (ref "TP_VP") (pin "1") (pinfunction "P$1_1") (pintype "bidirectional"))
    )
    (net (code "55") (name "VPPIN") (class "Default")
      (node (ref "R16") (pin "1") (pinfunction "1_1") (pintype "passive"))
    )
    (net (code "56") (name "unconnected-(J1-CT2-Pad1)") (class "Default")
      (node (ref "J1") (pin "1") (pinfunction "CT2_1") (pintype "bidirectional"))
    )
    (net (code "57") (name "unconnected-(J1-CT3-Pad7)") (class "Default")
      (node (ref "J1") (pin "7") (pinfunction "CT3_7") (pintype "bidirectional"))
    )
    (net (code "58") (name "unconnected-(J1-N{slash}C-PadX5)") (class "Default")
      (node (ref "J1") (pin "X5") (pinfunction "N/C_X5") (pintype "bidirectional"))
    )
    (net (code "59") (name "unconnected-(J1-TD2+-Pad3)") (class "Default")
      (node (ref "J1") (pin "3") (pinfunction "TD2+_3") (pintype "bidirectional"))
    )
    (net (code "60") (name "unconnected-(J1-TD2--Pad2)") (class "Default")
      (node (ref "J1") (pin "2") (pinfunction "TD2-_2") (pintype "bidirectional"))
    )
    (net (code "61") (name "unconnected-(J1-TD3+-Pad8)") (class "Default")
      (node (ref "J1") (pin "8") (pinfunction "TD3+_8") (pintype "bidirectional"))
    )
    (net (code "62") (name "unconnected-(J1-TD3--Pad9)") (class "Default")
      (node (ref "J1") (pin "9") (pinfunction "TD3-_9") (pintype "bidirectional"))
    )
    (net (code "63") (name "unconnected-(J1-VAUX-PadX3)") (class "Default")
      (node (ref "J1") (pin "X3") (pinfunction "VAUX_X3") (pintype "bidirectional"))
    )
    (net (code "64") (name "unconnected-(J3-LVP-Pad6)") (class "Default")
      (node (ref "J3") (pin "6") (pinfunction "LVP_6") (pintype "bidirectional"))
    )
    (net (code "65") (name "unconnected-(OSC1-NC-Pad2)") (class "Default")
      (node (ref "OSC1") (pin "2") (pinfunction "NC_2") (pintype "bidirectional"))
    )
    (net (code "66") (name "unconnected-(U3-OSC2{slash}CLKO-Pad40)") (class "Default")
      (node (ref "U3") (pin "40") (pinfunction "OSC2/CLKO_40") (pintype "passive"))
    )
    (net (code "67") (name "unconnected-(U3-RA2{slash}AN2{slash}VREF--Pad22)") (class "Default")
      (node (ref "U3") (pin "22") (pinfunction "RA2/AN2/VREF-_22") (pintype "passive"))
    )
    (net (code "68") (name "unconnected-(U3-RA3{slash}AN3{slash}VREF+-Pad21)") (class "Default")
      (node (ref "U3") (pin "21") (pinfunction "RA3/AN3/VREF+_21") (pintype "passive"))
    )
    (net (code "69") (name "unconnected-(U3-RA4{slash}T0CKI-Pad28)") (class "Default")
      (node (ref "U3") (pin "28") (pinfunction "RA4/T0CKI_28") (pintype "passive"))
    )
    (net (code "70") (name "unconnected-(U3-RA5{slash}AN4-Pad27)") (class "Default")
      (node (ref "U3") (pin "27") (pinfunction "RA5/AN4_27") (pintype "passive"))
    )
    (net (code "71") (name "unconnected-(U3-RB0{slash}INT0{slash}FLT0-Pad3)") (class "Default")
      (node (ref "U3") (pin "3") (pinfunction "RB0/INT0/FLT0_3") (pintype "passive"))
    )
    (net (code "72") (name "unconnected-(U3-RB1{slash}INT1-Pad4)") (class "Default")
      (node (ref "U3") (pin "4") (pinfunction "RB1/INT1_4") (pintype "passive"))
    )
    (net (code "73") (name "unconnected-(U3-RB3{slash}INT3-Pad6)") (class "Default")
      (node (ref "U3") (pin "6") (pinfunction "RB3/INT3_6") (pintype "passive"))
    )
    (net (code "74") (name "unconnected-(U3-RB5{slash}KBI1-Pad43)") (class "Default")
      (node (ref "U3") (pin "43") (pinfunction "RB5/KBI1_43") (pintype "passive"))
    )
    (net (code "75") (name "unconnected-(U3-RC0{slash}T1OSO{slash}T13CKI-Pad30)") (class "Default")
      (node (ref "U3") (pin "30") (pinfunction "RC0/T1OSO/T13CKI_30") (pintype "passive"))
    )
    (net (code "76") (name "unconnected-(U3-RC1{slash}T1OSI{slash}ECCP2{slash}P2A-Pad29)") (class "Default")
      (node (ref "U3") (pin "29") (pinfunction "RC1/T1OSI/ECCP2/P2A_29") (pintype "passive"))
    )
    (net (code "77") (name "unconnected-(U3-RC2{slash}ECCP1{slash}P1A-Pad33)") (class "Default")
      (node (ref "U3") (pin "33") (pinfunction "RC2/ECCP1/P1A_33") (pintype "passive"))
    )
    (net (code "78") (name "unconnected-(U3-RD0{slash}P1B-Pad60)") (class "Default")
      (node (ref "U3") (pin "60") (pinfunction "RD0/P1B_60") (pintype "passive"))
    )
    (net (code "79") (name "unconnected-(U3-RD1{slash}ECCP3{slash}P3A-Pad59)") (class "Default")
      (node (ref "U3") (pin "59") (pinfunction "RD1/ECCP3/P3A_59") (pintype "passive"))
    )
    (net (code "80") (name "unconnected-(U3-RD2{slash}CCP4{slash}P3D-Pad58)") (class "Default")
      (node (ref "U3") (pin "58") (pinfunction "RD2/CCP4/P3D_58") (pintype "passive"))
    )
    (net (code "81") (name "unconnected-(U3-RE0{slash}P2D-Pad2)") (class "Default")
      (node (ref "U3") (pin "2") (pinfunction "RE0/P2D_2") (pintype "passive"))
    )
    (net (code "82") (name "unconnected-(U3-RE1{slash}P2C-Pad1)") (class "Default")
      (node (ref "U3") (pin "1") (pinfunction "RE1/P2C_1") (pintype "passive"))
    )
    (net (code "83") (name "unconnected-(U3-RE3{slash}P3C-Pad63)") (class "Default")
      (node (ref "U3") (pin "63") (pinfunction "RE3/P3C_63") (pintype "passive"))
    )
    (net (code "84") (name "unconnected-(U3-RF1{slash}AN6{slash}C2OUT-Pad17)") (class "Default")
      (node (ref "U3") (pin "17") (pinfunction "RF1/AN6/C2OUT_17") (pintype "passive"))
    )
    (net (code "85") (name "unconnected-(U3-RF2{slash}AN7{slash}C1OUT-Pad16)") (class "Default")
      (node (ref "U3") (pin "16") (pinfunction "RF2/AN7/C1OUT_16") (pintype "passive"))
    )
    (net (code "86") (name "unconnected-(U3-RF3{slash}AN8-Pad15)") (class "Default")
      (node (ref "U3") (pin "15") (pinfunction "RF3/AN8_15") (pintype "passive"))
    )
    (net (code "87") (name "unconnected-(U3-RF4{slash}AN9-Pad14)") (class "Default")
      (node (ref "U3") (pin "14") (pinfunction "RF4/AN9_14") (pintype "passive"))
    )
    (net (code "88") (name "unconnected-(U3-RF5{slash}AN10{slash}CVREF-Pad13)") (class "Default")
      (node (ref "U3") (pin "13") (pinfunction "RF5/AN10/CVREF_13") (pintype "passive"))
    )
    (net (code "89") (name "unconnected-(U3-RF6{slash}AN11-Pad12)") (class "Default")
      (node (ref "U3") (pin "12") (pinfunction "RF6/AN11_12") (pintype "passive"))
    )
    (net (code "90") (name "unconnected-(U3-RF7{slash}~{SS1}-Pad11)") (class "Default")
      (node (ref "U3") (pin "11") (pinfunction "RF7/~{SS1}_11") (pintype "passive"))
    )
    (net (code "91") (name "unconnected-(U3-RG4{slash}CCP5{slash}P1D-Pad8)") (class "Default")
      (node (ref "U3") (pin "8") (pinfunction "RG4/CCP5/P1D_8") (pintype "passive"))
    )
    (net (code "92") (name "{slash}CDB") (class "Default")
      (node (ref "PS1") (pin "1") (pinfunction "CTRL_1") (pintype "input"))
      (node (ref "Q1") (pin "3") (pinfunction "D_3") (pintype "passive"))
    )
    (net (code "93") (name "{slash}MCLR") (class "Default")
      (node (ref "J3") (pin "1") (pinfunction "VPP/MCLR_1") (pintype "passive"))
      (node (ref "R28") (pin "2") (pinfunction "2_2") (pintype "passive"))
      (node (ref "U3") (pin "7") (pinfunction "~{MCLR}_7") (pintype "passive"))
    )
    (net (code "94") (name "{slash}PGOOD") (class "Default")
      (node (ref "D2") (pin "C") (pinfunction "C_C") (pintype "passive"))
      (node (ref "J1") (pin "X4") (pinfunction "PGOOD_X4") (pintype "bidirectional"))
      (node (ref "R2") (pin "1") (pinfunction "1_1") (pintype "passive"))
      (node (ref "R3") (pin "1") (pinfunction "1_1") (pintype "passive"))
    )
  )
)
